# 07-USB.net
KiCad netlist of a schematic drawn in Altium Designer
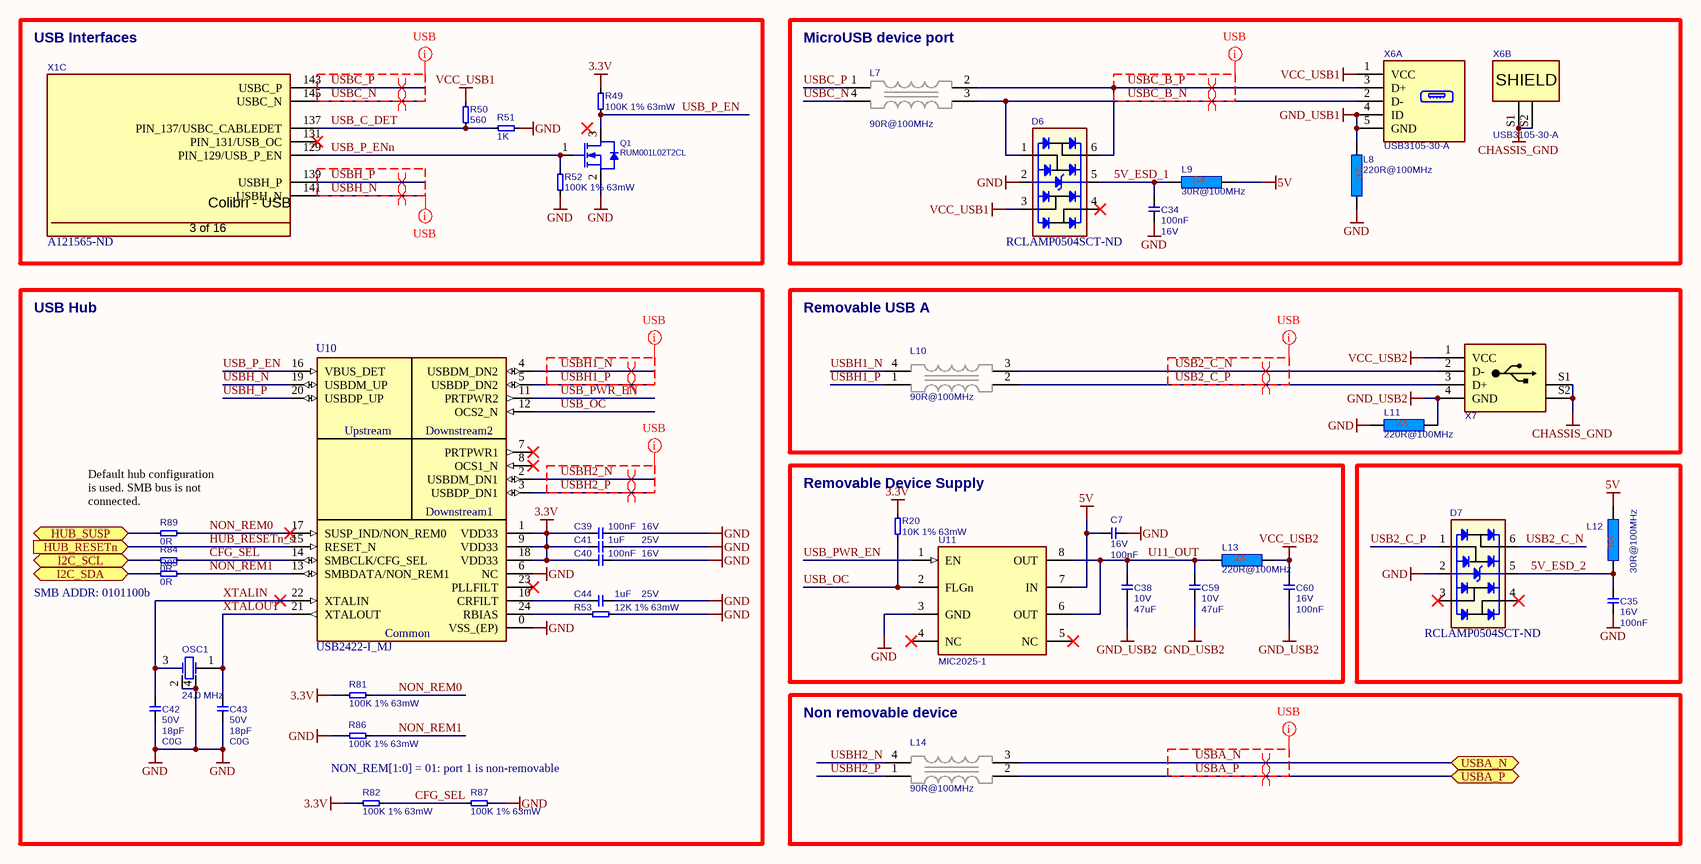
[diagram p0: 07-USB.SchDoc]

(export (version "E")
  (design (tool "Eeschema 10.0.6"))
  (components
    (comp (ref "C7")
      (value "100nF")
      (footprint "CAPC1005X60N")
      (description "Capacitor Ceramic X7R 100nF 16V 10% 0603")
      (fields
        (field (name "TOLERANCE") "10%")
        (field (name "RATING") "16V")
        (field (name "Comment") "100nF 16V 10% X7R")
      )
      (libsource (lib "AI Gateway - Carrier") (part "C-100nF-16V-10%-0603"))
    )
    (comp (ref "C34")
      (value "100nF")
      (footprint "CAPC1005X60N")
      (description "Capacitor Ceramic X7R 100nF 16V 10% 0603")
      (fields
        (field (name "TOLERANCE") "10%")
        (field (name "RATING") "16V")
        (field (name "Comment") "100nF 16V 10% X7R")
      )
      (libsource (lib "AI Gateway - Carrier") (part "C-100nF-16V-10%-0603"))
    )
    (comp (ref "C35")
      (value "100nF")
      (footprint "CAPC1005X60N")
      (description "Capacitor Ceramic X7R 100nF 16V 10% 0603")
      (fields
        (field (name "TOLERANCE") "10%")
        (field (name "RATING") "16V")
        (field (name "Comment") "100nF 16V 10% X7R")
      )
      (libsource (lib "AI Gateway - Carrier") (part "C-100nF-16V-10%-0603"))
    )
    (comp (ref "C38")
      (value "47uF")
      (footprint "CAPC3225X160N")
      (description "Capacitor Ceramic X5R 47uF 10V 20% 1210")
      (fields
        (field (name "TOLERANCE") "20%")
        (field (name "RATING") "10V")
        (field (name "Comment") "47uF 10V 20% X5R")
      )
      (libsource (lib "AI Gateway - Carrier") (part "C-47uF-10V-20%-1210"))
    )
    (comp (ref "C39")
      (value "100nF")
      (footprint "CAPC1005X60N")
      (description "Capacitor Ceramic X7R 100nF 16V 10% 0603")
      (fields
        (field (name "TOLERANCE") "10%")
        (field (name "RATING") "16V")
        (field (name "Comment") "100nF 16V 10% X7R")
      )
      (libsource (lib "AI Gateway - Carrier") (part "C-100nF-16V-10%-0603"))
    )
    (comp (ref "C40")
      (value "100nF")
      (footprint "CAPC1005X60N")
      (description "Capacitor Ceramic X7R 100nF 16V 10% 0603")
      (fields
        (field (name "TOLERANCE") "10%")
        (field (name "RATING") "16V")
        (field (name "Comment") "100nF 16V 10% X7R")
      )
      (libsource (lib "AI Gateway - Carrier") (part "C-100nF-16V-10%-0603"))
    )
    (comp (ref "C41")
      (value "1uF")
      (footprint "T_CAPC0805X125N")
      (description "Capacitor Ceramic X7R 1uF 25V 10% 0805")
      (fields
        (field (name "TOLERANCE") "10%")
        (field (name "RATING") "25V")
        (field (name "Comment") "1uF 25V 10% X7R")
      )
      (libsource (lib "AI Gateway - Carrier") (part "C-1uF-25V-10%-0805"))
    )
    (comp (ref "C42")
      (value "18pF")
      (footprint "T_CAPC0603X33N")
      (description "Capacitor Ceramic C0G 18pF 50V 5% 0603")
      (fields
        (field (name "TOLERANCE") "5%")
        (field (name "RATING") "50V")
        (field (name "TYPE") "C0G")
        (field (name "Comment") "18pF 50V 5% C0G")
      )
      (libsource (lib "AI Gateway - Carrier") (part "C-18pF-50V-5%-0603"))
    )
    (comp (ref "C43")
      (value "18pF")
      (footprint "T_CAPC0603X33N")
      (description "Capacitor Ceramic C0G 18pF 50V 5% 0603")
      (fields
        (field (name "TOLERANCE") "5%")
        (field (name "RATING") "50V")
        (field (name "TYPE") "C0G")
        (field (name "Comment") "18pF 50V 5% C0G")
      )
      (libsource (lib "AI Gateway - Carrier") (part "C-18pF-50V-5%-0603"))
    )
    (comp (ref "C44")
      (value "1uF")
      (footprint "T_CAPC0805X125N")
      (description "Capacitor Ceramic X7R 1uF 25V 10% 0805")
      (fields
        (field (name "TOLERANCE") "10%")
        (field (name "RATING") "25V")
        (field (name "Comment") "1uF 25V 10% X7R")
      )
      (libsource (lib "AI Gateway - Carrier") (part "C-1uF-25V-10%-0805"))
    )
    (comp (ref "C59")
      (value "47uF")
      (footprint "CAPC3225X160N")
      (description "Capacitor Ceramic X5R 47uF 10V 20% 1210")
      (fields
        (field (name "TOLERANCE") "20%")
        (field (name "RATING") "10V")
        (field (name "Comment") "47uF 10V 20% X5R")
      )
      (libsource (lib "AI Gateway - Carrier") (part "C-47uF-10V-20%-1210"))
    )
    (comp (ref "C60")
      (value "100nF")
      (footprint "CAPC1005X60N")
      (description "Capacitor Ceramic X7R 100nF 16V 10% 0603")
      (fields
        (field (name "TOLERANCE") "10%")
        (field (name "RATING") "16V")
        (field (name "Comment") "100nF 16V 10% X7R")
      )
      (libsource (lib "AI Gateway - Carrier") (part "C-100nF-16V-10%-0603"))
    )
    (comp (ref "D6")
      (value "RCLAMP0504S")
      (footprint "T_SOT95P285X90-6N")
      (description "TVS Array low cap")
      (fields (field (name "SUPPLIER PART NUMBER 1") "RCLAMP0504SCT-ND") (field (name "MFG") "Semtech"))
      (libsource (lib "Passive") (part "D-Semtech-RClamp0504S"))
    )
    (comp (ref "D7")
      (value "RCLAMP0504S")
      (footprint "T_SOT95P285X90-6N")
      (description "TVS Array low cap")
      (fields (field (name "SUPPLIER PART NUMBER 1") "RCLAMP0504SCT-ND") (field (name "MFG") "Semtech"))
      (libsource (lib "Passive") (part "D-Semtech-RClamp0504S"))
    )
    (comp (ref "L7")
      (value "90R@100MHz")
      (footprint "T_Murata_DLW21SN900SQ2")
      (description "Common Mode Choke High Speed 90R 330mA")
      (fields (field (name "TOLERANCE") "25%") (field (name "MFG") "Murata"))
      (libsource (lib "Passive") (part "L-Murata-DLW21SN900SQ2-90R@100MHz-330mA-25%"))
    )
    (comp (ref "L8")
      (value "220R@100MHz")
      (footprint "INDC2012X140N")
      (description "220 Ohms @ 100MHz 1 Power Line Ferrite Bead 0805 (2012 Metric) 2A 45mOhm")
      (fields (field (name "TOLERANCE") "25%") (field (name "MFG") "EXC-ML20A390U"))
      (libsource (lib "Passive") (part "L-Murata-220R@100MHz-2A-0805"))
    )
    (comp (ref "L9")
      (value "30R@100MHz")
      (footprint "INDC1608X95N")
      (description "30 Ohms @ 100MHz 1 Power Line Ferrite Bead 0603 (1608 Metric) 5A 10mOhm")
      (fields
        (field (name "TOLERANCE") "25%")
        (field (name "MFG") "EXC-ML20A390U")
        (field (name "FOOTPRINT CHECKED") "Ok, Assign Ok")
      )
      (libsource (lib "") (part "L-Murata-30R@100MHz-5A-0603_1"))
    )
    (comp (ref "L10")
      (value "90R@100MHz")
      (footprint "T_Murata_DLW21SN900SQ2")
      (description "Common Mode Choke High Speed 90R 330mA")
      (fields (field (name "TOLERANCE") "25%") (field (name "MFG") "Murata"))
      (libsource (lib "") (part "L-Murata-DLW21SN900SQ2-90R@100MHz-330mA-25%_1"))
    )
    (comp (ref "L11")
      (value "220R@100MHz")
      (footprint "INDC2012X140N")
      (description "220 Ohms @ 100MHz 1 Power Line Ferrite Bead 0805 (2012 Metric) 2A 45mOhm")
      (fields (field (name "TOLERANCE") "25%") (field (name "MFG") "EXC-ML20A390U"))
      (libsource (lib "") (part "L-Murata-220R@100MHz-2A-0805_1"))
    )
    (comp (ref "L12")
      (value "30R@100MHz")
      (footprint "INDC1608X95N")
      (description "30 Ohms @ 100MHz 1 Power Line Ferrite Bead 0603 (1608 Metric) 5A 10mOhm")
      (fields
        (field (name "TOLERANCE") "25%")
        (field (name "MFG") "EXC-ML20A390U")
        (field (name "FOOTPRINT CHECKED") "Ok, Assign Ok")
      )
      (libsource (lib "Passive") (part "L-Murata-30R@100MHz-5A-0603"))
    )
    (comp (ref "L13")
      (value "220R@100MHz")
      (footprint "INDC2012X140N")
      (description "220 Ohms @ 100MHz 1 Power Line Ferrite Bead 0805 (2012 Metric) 2A 45mOhm")
      (fields (field (name "TOLERANCE") "25%") (field (name "MFG") "EXC-ML20A390U"))
      (libsource (lib "") (part "L-Murata-220R@100MHz-2A-0805_1"))
    )
    (comp (ref "L14")
      (value "90R@100MHz")
      (footprint "T_Murata_DLW21SN900SQ2")
      (description "Common Mode Choke High Speed 90R 330mA")
      (fields (field (name "TOLERANCE") "25%") (field (name "MFG") "Murata"))
      (libsource (lib "") (part "L-Murata-DLW21SN900SQ2-90R@100MHz-330mA-25%_1"))
    )
    (comp (ref "OSC1")
      (value "24.0 MHz")
      (footprint "XTAL3.2x2.5")
      (description "24MHz ±20ppm Crystal 18pF 60 Ohms 4-SMD, No Lead")
      (fields (field (name "TOLERANCE") "30ppm") (field (name "MFG") "HORIZON"))
      (libsource (lib "Passive") (part "OSC-ABM8G-24.000MHZ-18-D2Y-T"))
    )
    (comp (ref "Q1")
      (value "RUM001L02T2CL")
      (footprint "TRANS_RUM001_ROM")
      (description "N-Channel 20V 100mA (Ta) 150mW (Ta) Surface Mount VMT3")
      (fields (field (name "MFG") "Rohm Semiconductor Inc."))
      (libsource (lib "Passive") (part "T-Rohm-RUM001L02T2CL"))
    )
    (comp (ref "R20")
      (value "10K 1% 63mW")
      (footprint "RESC1005X40N")
      (description "Resistor 10Kohm 63mW 1% 0402")
      (fields (field (name "POWER") "63mW") (field (name "TOLERANCE") "1%"))
      (libsource (lib "AI Gateway - Carrier") (part "R-10K-1%-0402"))
    )
    (comp (ref "R49")
      (value "100K 1% 63mW")
      (footprint "RESC1005X40N")
      (description "Resistor 100Kohm 63mW 1% 0402")
      (fields (field (name "POWER") "63mW") (field (name "TOLERANCE") "1%"))
      (libsource (lib "AI Gateway - Carrier") (part "R-100K-1%-0402"))
    )
    (comp (ref "R50")
      (value "560")
      (footprint "RESC1005X40N")
      (description "Resistor 560ohm 63mW 1% 0402")
      (fields (field (name "TOLERANCE") "1%") (field (name "POWER") "63mW"))
      (libsource (lib "AI Gateway - Carrier") (part "R-560R-1%-0402"))
    )
    (comp (ref "R51")
      (value "1K")
      (footprint "RESC1005X40N")
      (description "Resistor 1Kohm 63mW 1% 0402")
      (fields (field (name "TOLERANCE") "1%") (field (name "POWER") "63mW"))
      (libsource (lib "AI Gateway - Carrier") (part "R-1K-1%-0402"))
    )
    (comp (ref "R52")
      (value "100K 1% 63mW")
      (footprint "RESC1005X40N")
      (description "Resistor 100Kohm 63mW 1% 0402")
      (fields (field (name "TOLERANCE") "1%") (field (name "POWER") "63mW"))
      (libsource (lib "AI Gateway - Carrier") (part "R-100K-1%-0402"))
    )
    (comp (ref "R53")
      (value "12K 1% 63mW")
      (footprint "RESC1005X40N")
      (description "Resistor 12Kohm 63mW 1% 0402")
      (fields
        (field (name "TOLERANCE") "1%")
        (field (name "POWER") "63mW")
        (field (name "SYMBOL CHECKED") "T")
      )
      (libsource (lib "AI Gateway - Carrier") (part "R-12K-1%-0402"))
    )
    (comp (ref "R81")
      (value "100K 1% 63mW")
      (footprint "RESC1005X40N")
      (description "Resistor 100Kohm 63mW 1% 0402")
      (fields (field (name "POWER") "63mW") (field (name "TOLERANCE") "1%"))
      (libsource (lib "AI Gateway - Carrier") (part "R-100K-1%-0402"))
    )
    (comp (ref "R82")
      (value "100K 1% 63mW")
      (footprint "RESC1005X40N")
      (description "Resistor 100Kohm 63mW 1% 0402")
      (fields (field (name "POWER") "63mW") (field (name "TOLERANCE") "1%"))
      (libsource (lib "AI Gateway - Carrier") (part "R-100K-1%-0402"))
    )
    (comp (ref "R84")
      (value "0R")
      (footprint "RESC1005X40N")
      (description "Resistor 0ohm 0402")
      (fields (field (name "POWER") "?") (field (name "TOLERANCE") "1%"))
      (libsource (lib "AI Gateway - Carrier") (part "R-0R-0402"))
    )
    (comp (ref "R85")
      (value "0R")
      (footprint "RESC1005X40N")
      (description "Resistor 0ohm 0402")
      (fields (field (name "POWER") "?") (field (name "TOLERANCE") "1%"))
      (libsource (lib "AI Gateway - Carrier") (part "R-0R-0402"))
    )
    (comp (ref "R86")
      (value "100K 1% 63mW")
      (footprint "RESC1005X40N")
      (description "Resistor 100Kohm 63mW 1% 0402")
      (fields (field (name "POWER") "63mW") (field (name "TOLERANCE") "1%"))
      (libsource (lib "AI Gateway - Carrier") (part "R-100K-1%-0402"))
    )
    (comp (ref "R87")
      (value "100K 1% 63mW")
      (footprint "RESC1005X40N")
      (description "Resistor 100Kohm 63mW 1% 0402")
      (fields (field (name "POWER") "63mW") (field (name "TOLERANCE") "1%"))
      (libsource (lib "AI Gateway - Carrier") (part "R-100K-1%-0402"))
    )
    (comp (ref "R89")
      (value "0R")
      (footprint "RESC1005X40N")
      (description "Resistor 0ohm 0402")
      (fields (field (name "POWER") "?") (field (name "TOLERANCE") "1%"))
      (libsource (lib "AI Gateway - Carrier") (part "R-0R-0402"))
    )
    (comp (ref "U10")
      (value "USB2422-I_MJ")
      (footprint "QFN50P400X400X80-25N")
      (description "USB Hub Controller USB 2.0 USB Interface 24-QFN (4x4)")
      (libsource (lib "AIGateway") (part "IC-Microchip-USB2422-I_MJ"))
    )
    (comp (ref "U11")
      (value "MIC2025-1")
      (footprint "SOIC127P600X175-8N")
      (description "Power Switch/Driver 1:1 N-Channel 500mA 8-MSOP")
      (fields (field (name "MFG") "Texas Instruments") (field (name "SYMBOL CHECKED") "T"))
      (libsource (lib "AIGateway") (part "IC-Microchip-MIC2025-1"))
    )
    (comp (ref "X1")
      (value "1473005-1")
      (footprint "T_Tyco_1473005-1")
      (description "SODIMM Connector")
      (fields (field (name "SUPPLIER PART NUMBER 1") "A121565-ND"))
      (libsource (lib "Connectors") (part "CON-Tyco-1473005-1-200-0.6mm"))
    )
    (comp (ref "X6")
      (value "USB3105-30-A")
      (footprint "T_GCT_USB3105-30-A")
      (description "Micro USB OTG Connector - TH - Vertical")
      (fields (field (name "MFG") "GCT"))
      (libsource (lib "") (part "CON-GCT-USB3105-30-A_1"))
    )
    (comp (ref "X7")
      (value "UE27AE54100")
      (footprint "T_FCI_UE27AE54100")
      (description "USB Type A Connector")
      (libsource (lib "Connectors") (part "CON-FCI-UE27AE54100"))
    )
  )
  (nets
    (net (code "1") (name "/5V_ESD_1") (class "Default")
      (node (ref "C34") (pin "2") (pinfunction "2_2") (pintype "passive"))
      (node (ref "D6") (pin "5") (pinfunction "5_5") (pintype "power_in"))
      (node (ref "L9") (pin "2") (pinfunction "2_2") (pintype "passive"))
    )
    (net (code "2") (name "/5V_ESD_2") (class "Default")
      (node (ref "C35") (pin "2") (pinfunction "2_2") (pintype "passive"))
      (node (ref "D7") (pin "5") (pinfunction "5_5") (pintype "power_in"))
      (node (ref "L12") (pin "2") (pinfunction "2_2") (pintype "passive"))
    )
    (net (code "3") (name "/CFG_SEL") (class "Default")
      (node (ref "R82") (pin "1") (pinfunction "1_1") (pintype "passive"))
      (node (ref "R84") (pin "1") (pinfunction "1_1") (pintype "passive"))
      (node (ref "R87") (pin "2") (pinfunction "2_2") (pintype "passive"))
      (node (ref "U10") (pin "14") (pinfunction "SMBCLK/CFG_SEL_14") (pintype "bidirectional"))
    )
    (net (code "4") (name "/HUB_RESETn_s") (class "Default")
      (node (ref "U10") (pin "15") (pinfunction "RESET_N_15") (pintype "input"))
    )
    (net (code "5") (name "/HUB_SUSP") (class "Default")
      (node (ref "R89") (pin "2") (pinfunction "2_2") (pintype "passive"))
    )
    (net (code "6") (name "/I2C_SCL") (class "Default")
      (node (ref "R84") (pin "2") (pinfunction "2_2") (pintype "passive"))
    )
    (net (code "7") (name "/I2C_SDA") (class "Default")
      (node (ref "R85") (pin "2") (pinfunction "2_2") (pintype "passive"))
    )
    (net (code "8") (name "/NON_REM0") (class "Default")
      (node (ref "R81") (pin "1") (pinfunction "1_1") (pintype "passive"))
      (node (ref "R89") (pin "1") (pinfunction "1_1") (pintype "passive"))
      (node (ref "U10") (pin "17") (pinfunction "SUSP_IND/NON_REM0_17") (pintype "input"))
    )
    (net (code "9") (name "/NON_REM1") (class "Default")
      (node (ref "R85") (pin "1") (pinfunction "1_1") (pintype "passive"))
      (node (ref "R86") (pin "2") (pinfunction "2_2") (pintype "passive"))
      (node (ref "U10") (pin "13") (pinfunction "SMBDATA/NON_REM1_13") (pintype "bidirectional"))
    )
    (net (code "10") (name "/U11_OUT") (class "Default")
      (node (ref "C38") (pin "2") (pinfunction "2_2") (pintype "passive"))
      (node (ref "C59") (pin "2") (pinfunction "2_2") (pintype "passive"))
      (node (ref "L13") (pin "2") (pinfunction "2_2") (pintype "passive"))
      (node (ref "U11") (pin "6") (pinfunction "OUT_6") (pintype "power_in"))
      (node (ref "U11") (pin "8") (pinfunction "OUT_8") (pintype "power_in"))
    )
    (net (code "11") (name "/USB2_C_N") (class "Default")
      (node (ref "D7") (pin "6") (pinfunction "6_6") (pintype "passive"))
      (node (ref "L10") (pin "3") (pinfunction "3_3") (pintype "passive"))
      (node (ref "X7") (pin "2") (pinfunction "D-_2") (pintype "passive"))
    )
    (net (code "12") (name "/USB2_C_P") (class "Default")
      (node (ref "D7") (pin "1") (pinfunction "1_1") (pintype "passive"))
      (node (ref "L10") (pin "2") (pinfunction "2_2") (pintype "passive"))
      (node (ref "X7") (pin "3") (pinfunction "D+_3") (pintype "passive"))
    )
    (net (code "13") (name "/USBA_N") (class "Default")
      (node (ref "L14") (pin "3") (pinfunction "3_3") (pintype "passive"))
    )
    (net (code "14") (name "/USBA_P") (class "Default")
      (node (ref "L14") (pin "2") (pinfunction "2_2") (pintype "passive"))
    )
    (net (code "15") (name "/USBC_B_N") (class "Default")
      (node (ref "D6") (pin "1") (pinfunction "1_1") (pintype "passive"))
      (node (ref "L7") (pin "3") (pinfunction "3_3") (pintype "passive"))
      (node (ref "X6") (pin "2") (pinfunction "D-_2") (pintype "passive"))
    )
    (net (code "16") (name "/USBC_B_P") (class "Default")
      (node (ref "D6") (pin "6") (pinfunction "6_6") (pintype "passive"))
      (node (ref "L7") (pin "2") (pinfunction "2_2") (pintype "passive"))
      (node (ref "X6") (pin "3") (pinfunction "D+_3") (pintype "passive"))
    )
    (net (code "17") (name "/USBC_N") (class "Default")
      (node (ref "L7") (pin "4") (pinfunction "4_4") (pintype "passive"))
      (node (ref "X1") (pin "145") (pinfunction "USBC_N_145") (pintype "passive"))
    )
    (net (code "18") (name "/USBC_P") (class "Default")
      (node (ref "L7") (pin "1") (pinfunction "1_1") (pintype "passive"))
      (node (ref "X1") (pin "143") (pinfunction "USBC_P_143") (pintype "passive"))
    )
    (net (code "19") (name "/USBH1_N") (class "Default")
      (node (ref "L10") (pin "4") (pinfunction "4_4") (pintype "passive"))
      (node (ref "U10") (pin "4") (pinfunction "USBDM_DN2_4") (pintype "bidirectional"))
    )
    (net (code "20") (name "/USBH1_P") (class "Default")
      (node (ref "L10") (pin "1") (pinfunction "1_1") (pintype "passive"))
      (node (ref "U10") (pin "5") (pinfunction "USBDP_DN2_5") (pintype "bidirectional"))
    )
    (net (code "21") (name "/USBH2_N") (class "Default")
      (node (ref "L14") (pin "4") (pinfunction "4_4") (pintype "passive"))
      (node (ref "U10") (pin "2") (pinfunction "USBDM_DN1_2") (pintype "bidirectional"))
    )
    (net (code "22") (name "/USBH2_P") (class "Default")
      (node (ref "L14") (pin "1") (pinfunction "1_1") (pintype "passive"))
      (node (ref "U10") (pin "3") (pinfunction "USBDP_DN1_3") (pintype "bidirectional"))
    )
    (net (code "23") (name "/USBH_N") (class "Default")
      (node (ref "U10") (pin "19") (pinfunction "USBDM_UP_19") (pintype "bidirectional"))
      (node (ref "X1") (pin "141") (pinfunction "USBH_N_141") (pintype "passive"))
    )
    (net (code "24") (name "/USBH_P") (class "Default")
      (node (ref "U10") (pin "20") (pinfunction "USBDP_UP_20") (pintype "bidirectional"))
      (node (ref "X1") (pin "139") (pinfunction "USBH_P_139") (pintype "passive"))
    )
    (net (code "25") (name "/USB_C_DET") (class "Default")
      (node (ref "R50") (pin "2") (pinfunction "2_2") (pintype "passive"))
      (node (ref "R51") (pin "1") (pinfunction "1_1") (pintype "passive"))
      (node (ref "X1") (pin "137") (pinfunction "PIN_137/USBC_CABLEDET_137") (pintype "passive"))
    )
    (net (code "26") (name "/USB_OC") (class "Default")
      (node (ref "R20") (pin "2") (pinfunction "2_2") (pintype "passive"))
      (node (ref "U10") (pin "12") (pinfunction "OCS2_N_12") (pintype "input"))
      (node (ref "U11") (pin "2") (pinfunction "FLGn_2") (pintype "open_collector"))
    )
    (net (code "27") (name "/USB_PWR_EN") (class "Default")
      (node (ref "U10") (pin "11") (pinfunction "PRTPWR2_11") (pintype "output"))
      (node (ref "U11") (pin "1") (pinfunction "EN_1") (pintype "input"))
    )
    (net (code "28") (name "/USB_P_EN") (class "Default")
      (node (ref "Q1") (pin "3") (pinfunction "S_3") (pintype "passive"))
      (node (ref "R49") (pin "1") (pinfunction "1_1") (pintype "passive"))
      (node (ref "U10") (pin "16") (pinfunction "VBUS_DET_16") (pintype "input"))
    )
    (net (code "29") (name "/USB_P_ENn") (class "Default")
      (node (ref "Q1") (pin "1") (pinfunction "G_1") (pintype "passive"))
      (node (ref "R52") (pin "1") (pinfunction "1_1") (pintype "passive"))
      (node (ref "X1") (pin "129") (pinfunction "PIN_129/USB_P_EN_129") (pintype "passive"))
    )
    (net (code "30") (name "/XTALIN") (class "Default")
      (node (ref "C42") (pin "2") (pinfunction "2_2") (pintype "passive"))
      (node (ref "OSC1") (pin "3") (pinfunction "OSC2_3") (pintype "passive"))
      (node (ref "U10") (pin "22") (pinfunction "XTALIN_22") (pintype "input"))
    )
    (net (code "31") (name "/XTALOUT") (class "Default")
      (node (ref "C43") (pin "2") (pinfunction "2_2") (pintype "passive"))
      (node (ref "OSC1") (pin "1") (pinfunction "OSC1_1") (pintype "passive"))
      (node (ref "U10") (pin "21") (pinfunction "XTALOUT_21") (pintype "output"))
    )
    (net (code "32") (name "3.3V") (class "Default")
      (node (ref "C39") (pin "2") (pinfunction "2_2") (pintype "passive"))
      (node (ref "C40") (pin "2") (pinfunction "2_2") (pintype "passive"))
      (node (ref "C41") (pin "2") (pinfunction "2_2") (pintype "passive"))
      (node (ref "R20") (pin "1") (pinfunction "1_1") (pintype "passive"))
      (node (ref "R49") (pin "2") (pinfunction "2_2") (pintype "passive"))
      (node (ref "R81") (pin "2") (pinfunction "2_2") (pintype "passive"))
      (node (ref "R82") (pin "2") (pinfunction "2_2") (pintype "passive"))
      (node (ref "U10") (pin "1") (pinfunction "VDD33_1") (pintype "power_in"))
      (node (ref "U10") (pin "18") (pinfunction "VDD33_18") (pintype "power_in"))
      (node (ref "U10") (pin "9") (pinfunction "VDD33_9") (pintype "power_in"))
    )
    (net (code "33") (name "5V") (class "Default")
      (node (ref "C7") (pin "2") (pinfunction "2_2") (pintype "passive"))
      (node (ref "L12") (pin "1") (pinfunction "1_1") (pintype "passive"))
      (node (ref "L9") (pin "1") (pinfunction "1_1") (pintype "passive"))
      (node (ref "U11") (pin "7") (pinfunction "IN_7") (pintype "power_in"))
    )
    (net (code "34") (name "CHASSIS_GND") (class "Default")
      (node (ref "X6") (pin "S1") (pinfunction "SHIELD_S1") (pintype "passive"))
      (node (ref "X6") (pin "S2") (pinfunction "SHIELD_S2") (pintype "passive"))
      (node (ref "X7") (pin "S1") (pintype "passive"))
      (node (ref "X7") (pin "S2") (pintype "passive"))
    )
    (net (code "35") (name "GND") (class "Default")
      (node (ref "C34") (pin "1") (pinfunction "1_1") (pintype "passive"))
      (node (ref "C35") (pin "1") (pinfunction "1_1") (pintype "passive"))
      (node (ref "C39") (pin "1") (pinfunction "1_1") (pintype "passive"))
      (node (ref "C40") (pin "1") (pinfunction "1_1") (pintype "passive"))
      (node (ref "C41") (pin "1") (pinfunction "1_1") (pintype "passive"))
      (node (ref "C42") (pin "1") (pinfunction "1_1") (pintype "passive"))
      (node (ref "C43") (pin "1") (pinfunction "1_1") (pintype "passive"))
      (node (ref "C44") (pin "1") (pinfunction "1_1") (pintype "passive"))
      (node (ref "C7") (pin "1") (pinfunction "1_1") (pintype "passive"))
      (node (ref "D6") (pin "2") (pinfunction "2_2") (pintype "power_in"))
      (node (ref "D7") (pin "2") (pinfunction "2_2") (pintype "power_in"))
      (node (ref "L11") (pin "2") (pinfunction "2_2") (pintype "passive"))
      (node (ref "L8") (pin "1") (pinfunction "1_1") (pintype "passive"))
      (node (ref "OSC1") (pin "2") (pinfunction "2_2") (pintype "passive"))
      (node (ref "OSC1") (pin "4") (pinfunction "4_4") (pintype "passive"))
      (node (ref "Q1") (pin "2") (pinfunction "D_2") (pintype "passive"))
      (node (ref "R51") (pin "2") (pinfunction "2_2") (pintype "passive"))
      (node (ref "R52") (pin "2") (pinfunction "2_2") (pintype "passive"))
      (node (ref "R53") (pin "2") (pinfunction "2_2") (pintype "passive"))
      (node (ref "R86") (pin "1") (pinfunction "1_1") (pintype "passive"))
      (node (ref "R87") (pin "1") (pinfunction "1_1") (pintype "passive"))
      (node (ref "U10") (pin "0") (pinfunction "VSS_(EP)_0") (pintype "power_in"))
      (node (ref "U10") (pin "6") (pinfunction "NC_6") (pintype "passive"))
      (node (ref "U11") (pin "3") (pinfunction "GND_3") (pintype "power_in"))
    )
    (net (code "36") (name "GND_USB1") (class "Default")
      (node (ref "L8") (pin "2") (pinfunction "2_2") (pintype "passive"))
      (node (ref "X6") (pin "4") (pinfunction "ID_4") (pintype "passive"))
      (node (ref "X6") (pin "5") (pinfunction "GND_5") (pintype "power_in"))
    )
    (net (code "37") (name "GND_USB2") (class "Default")
      (node (ref "C38") (pin "1") (pinfunction "1_1") (pintype "passive"))
      (node (ref "C59") (pin "1") (pinfunction "1_1") (pintype "passive"))
      (node (ref "C60") (pin "1") (pinfunction "1_1") (pintype "passive"))
      (node (ref "L11") (pin "1") (pinfunction "1_1") (pintype "passive"))
      (node (ref "X7") (pin "4") (pinfunction "GND_4") (pintype "power_in"))
    )
    (net (code "38") (name "Net-(U10-CRFILT)") (class "Default")
      (node (ref "C44") (pin "2") (pinfunction "2_2") (pintype "passive"))
      (node (ref "U10") (pin "10") (pinfunction "CRFILT_10") (pintype "passive"))
    )
    (net (code "39") (name "Net-(U10-RBIAS)") (class "Default")
      (node (ref "R53") (pin "1") (pinfunction "1_1") (pintype "passive"))
      (node (ref "U10") (pin "24") (pinfunction "RBIAS_24") (pintype "passive"))
    )
    (net (code "40") (name "VCC_USB1") (class "Default")
      (node (ref "D6") (pin "3") (pinfunction "3_3") (pintype "passive"))
      (node (ref "R50") (pin "1") (pinfunction "1_1") (pintype "passive"))
      (node (ref "X6") (pin "1") (pinfunction "VCC_1") (pintype "power_in"))
    )
    (net (code "41") (name "VCC_USB2") (class "Default")
      (node (ref "C60") (pin "2") (pinfunction "2_2") (pintype "passive"))
      (node (ref "L13") (pin "1") (pinfunction "1_1") (pintype "passive"))
      (node (ref "X7") (pin "1") (pinfunction "VCC_1") (pintype "power_in"))
    )
    (net (code "42") (name "unconnected-(D6-Pad4)") (class "Default")
      (node (ref "D6") (pin "4") (pinfunction "4_4") (pintype "passive+no_connect"))
    )
    (net (code "43") (name "unconnected-(D7-Pad3)") (class "Default")
      (node (ref "D7") (pin "3") (pinfunction "3_3") (pintype "passive+no_connect"))
    )
    (net (code "44") (name "unconnected-(D7-Pad4)") (class "Default")
      (node (ref "D7") (pin "4") (pinfunction "4_4") (pintype "passive+no_connect"))
    )
    (net (code "45") (name "unconnected-(U10-OCS1_N-Pad8)") (class "Default")
      (node (ref "U10") (pin "8") (pinfunction "OCS1_N_8") (pintype "input+no_connect"))
    )
    (net (code "46") (name "unconnected-(U10-PLLFILT-Pad23)") (class "Default")
      (node (ref "U10") (pin "23") (pinfunction "PLLFILT_23") (pintype "passive+no_connect"))
    )
    (net (code "47") (name "unconnected-(U10-PRTPWR1-Pad7)") (class "Default")
      (node (ref "U10") (pin "7") (pinfunction "PRTPWR1_7") (pintype "output+no_connect"))
    )
    (net (code "48") (name "unconnected-(U11-NC-Pad4)") (class "Default")
      (node (ref "U11") (pin "4") (pinfunction "NC_4") (pintype "tri_state+no_connect"))
    )
    (net (code "49") (name "unconnected-(U11-NC-Pad5)") (class "Default")
      (node (ref "U11") (pin "5") (pinfunction "NC_5") (pintype "tri_state+no_connect"))
    )
    (net (code "50") (name "unconnected-(X1C-PIN_131{slash}USB_OC-Pad131)") (class "Default")
      (node (ref "X1") (pin "131") (pinfunction "PIN_131/USB_OC_131") (pintype "passive+no_connect"))
    )
  )
)
